# Eagle-V2-SunSensor.net
KiCad netlist of a schematic drawn in EAGLE
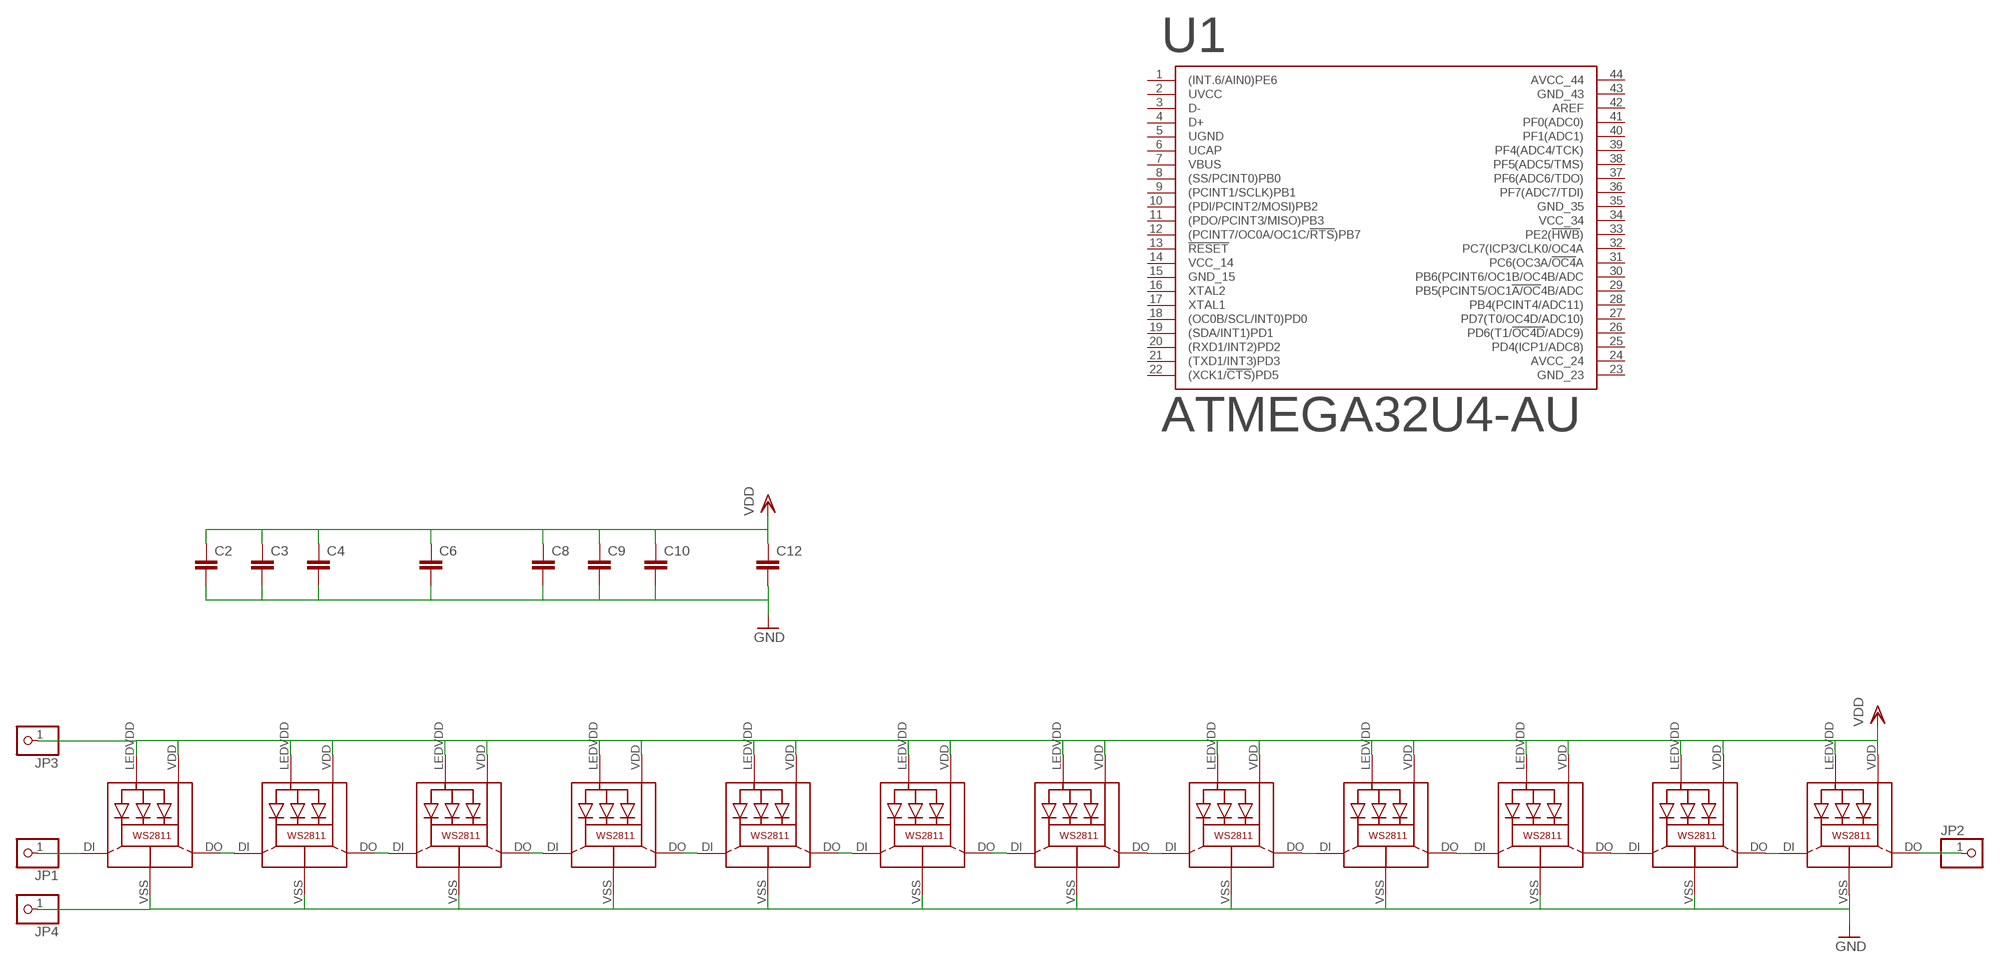
[diagram p0: schematic, sheet 1]

(export (version "E")
  (design (tool "Eeschema 10.0.6"))
  (components
    (comp (ref "C2")
      (value "C-EUC0603")
      (footprint "eagle-import:C0603")
      (libsource (lib "eagle-import") (part "C-EUC0603"))
    )
    (comp (ref "C3")
      (value "C-EUC0603")
      (footprint "eagle-import:C0603")
      (libsource (lib "eagle-import") (part "C-EUC0603"))
    )
    (comp (ref "C4")
      (value "C-EUC0603")
      (footprint "eagle-import:C0603")
      (libsource (lib "eagle-import") (part "C-EUC0603"))
    )
    (comp (ref "C6")
      (value "C-EUC0603")
      (footprint "eagle-import:C0603")
      (libsource (lib "eagle-import") (part "C-EUC0603"))
    )
    (comp (ref "C8")
      (value "C-EUC0603")
      (footprint "eagle-import:C0603")
      (libsource (lib "eagle-import") (part "C-EUC0603"))
    )
    (comp (ref "C9")
      (value "C-EUC0603")
      (footprint "eagle-import:C0603")
      (libsource (lib "eagle-import") (part "C-EUC0603"))
    )
    (comp (ref "C10")
      (value "C-EUC0603")
      (footprint "eagle-import:C0603")
      (libsource (lib "eagle-import") (part "C-EUC0603"))
    )
    (comp (ref "C12")
      (value "C-EUC0603")
      (footprint "eagle-import:C0603")
      (libsource (lib "eagle-import") (part "C-EUC0603"))
    )
    (comp (ref "JP1")
      (value "PINHD-1X1CB")
      (footprint "eagle-import:1X01-CLEANBIG")
      (libsource (lib "eagle-import") (part "PINHD-1X1CB"))
    )
    (comp (ref "JP2")
      (value "PINHD-1X1CB")
      (footprint "eagle-import:1X01-CLEANBIG")
      (libsource (lib "eagle-import") (part "PINHD-1X1CB"))
    )
    (comp (ref "JP3")
      (value "PINHD-1X1CB")
      (footprint "eagle-import:1X01-CLEANBIG")
      (libsource (lib "eagle-import") (part "PINHD-1X1CB"))
    )
    (comp (ref "JP4")
      (value "PINHD-1X1CB")
      (footprint "eagle-import:1X01-CLEANBIG")
      (libsource (lib "eagle-import") (part "PINHD-1X1CB"))
    )
    (comp (ref "LED1")
      (value "WS28115050")
      (footprint "eagle-import:WS28115050")
      (libsource (lib "eagle-import") (part "WS28115050"))
    )
    (comp (ref "LED2")
      (value "WS28115050")
      (footprint "eagle-import:WS28115050")
      (libsource (lib "eagle-import") (part "WS28115050"))
    )
    (comp (ref "LED3")
      (value "WS28115050")
      (footprint "eagle-import:WS28115050")
      (libsource (lib "eagle-import") (part "WS28115050"))
    )
    (comp (ref "LED4")
      (value "WS28115050")
      (footprint "eagle-import:WS28115050")
      (libsource (lib "eagle-import") (part "WS28115050"))
    )
    (comp (ref "LED5")
      (value "WS28115050")
      (footprint "eagle-import:WS28115050")
      (libsource (lib "eagle-import") (part "WS28115050"))
    )
    (comp (ref "LED6")
      (value "WS28115050")
      (footprint "eagle-import:WS28115050")
      (libsource (lib "eagle-import") (part "WS28115050"))
    )
    (comp (ref "LED7")
      (value "WS28115050")
      (footprint "eagle-import:WS28115050")
      (libsource (lib "eagle-import") (part "WS28115050"))
    )
    (comp (ref "LED8")
      (value "WS28115050")
      (footprint "eagle-import:WS28115050")
      (libsource (lib "eagle-import") (part "WS28115050"))
    )
    (comp (ref "LED9")
      (value "WS28115050")
      (footprint "eagle-import:WS28115050")
      (libsource (lib "eagle-import") (part "WS28115050"))
    )
    (comp (ref "LED10")
      (value "WS28115050")
      (footprint "eagle-import:WS28115050")
      (libsource (lib "eagle-import") (part "WS28115050"))
    )
    (comp (ref "LED11")
      (value "WS28115050")
      (footprint "eagle-import:WS28115050")
      (libsource (lib "eagle-import") (part "WS28115050"))
    )
    (comp (ref "LED12")
      (value "WS28115050")
      (footprint "eagle-import:WS28115050")
      (libsource (lib "eagle-import") (part "WS28115050"))
    )
    (comp (ref "U1")
      (value "ATMEGA32U4-AU")
      (footprint "eagle-import:44-TQFP")
      (fields
        (field (name "DIGIKEY_PART_NUMBER") "ATMEGA32U4-AU-ND")
        (field (name "MANUFACTURER") "Microchip Technology")
        (field (name "CREATED_BY") "PCBLayout.com")
      )
      (libsource (lib "eagle-import") (part "ATMEGA32U4-AU"))
    )
  )
  (nets
    (net (code "1") (name "/AVCC_24") (class "Default")
      (node (ref "U1") (pin "24") (pinfunction "AVCC_24_24") (pintype "power_in"))
    )
    (net (code "2") (name "/AVCC_44") (class "Default")
      (node (ref "U1") (pin "44") (pinfunction "AVCC_44_44") (pintype "power_in"))
    )
    (net (code "3") (name "/GND_15") (class "Default")
      (node (ref "U1") (pin "15") (pinfunction "GND_15_15") (pintype "power_in"))
    )
    (net (code "4") (name "/GND_23") (class "Default")
      (node (ref "U1") (pin "23") (pinfunction "GND_23_23") (pintype "power_in"))
    )
    (net (code "5") (name "/GND_35") (class "Default")
      (node (ref "U1") (pin "35") (pinfunction "GND_35_35") (pintype "power_in"))
    )
    (net (code "6") (name "/GND_43") (class "Default")
      (node (ref "U1") (pin "43") (pinfunction "GND_43_43") (pintype "power_in"))
    )
    (net (code "7") (name "/UCAP") (class "Default")
      (node (ref "U1") (pin "6") (pinfunction "UCAP_6") (pintype "power_in"))
    )
    (net (code "8") (name "/UGND") (class "Default")
      (node (ref "U1") (pin "5") (pinfunction "UGND_5") (pintype "power_in"))
    )
    (net (code "9") (name "/UVCC") (class "Default")
      (node (ref "U1") (pin "2") (pinfunction "UVCC_2") (pintype "power_in"))
    )
    (net (code "10") (name "/VCC_14") (class "Default")
      (node (ref "U1") (pin "14") (pinfunction "VCC_14_14") (pintype "power_in"))
    )
    (net (code "11") (name "/VCC_34") (class "Default")
      (node (ref "U1") (pin "34") (pinfunction "VCC_34_34") (pintype "power_in"))
    )
    (net (code "12") (name "GND") (class "Default")
      (node (ref "C10") (pin "2") (pinfunction "2_2") (pintype "passive"))
      (node (ref "C12") (pin "2") (pinfunction "2_2") (pintype "passive"))
      (node (ref "C2") (pin "2") (pinfunction "2_2") (pintype "passive"))
      (node (ref "C3") (pin "2") (pinfunction "2_2") (pintype "passive"))
      (node (ref "C4") (pin "2") (pinfunction "2_2") (pintype "passive"))
      (node (ref "C6") (pin "2") (pinfunction "2_2") (pintype "passive"))
      (node (ref "C8") (pin "2") (pinfunction "2_2") (pintype "passive"))
      (node (ref "C9") (pin "2") (pinfunction "2_2") (pintype "passive"))
      (node (ref "JP4") (pin "1") (pinfunction "1_1") (pintype "passive"))
      (node (ref "LED1") (pin "VSS") (pinfunction "GND_VSS") (pintype "power_in"))
      (node (ref "LED10") (pin "VSS") (pinfunction "GND_VSS") (pintype "power_in"))
      (node (ref "LED11") (pin "VSS") (pinfunction "GND_VSS") (pintype "power_in"))
      (node (ref "LED12") (pin "VSS") (pinfunction "GND_VSS") (pintype "power_in"))
      (node (ref "LED2") (pin "VSS") (pinfunction "GND_VSS") (pintype "power_in"))
      (node (ref "LED3") (pin "VSS") (pinfunction "GND_VSS") (pintype "power_in"))
      (node (ref "LED4") (pin "VSS") (pinfunction "GND_VSS") (pintype "power_in"))
      (node (ref "LED5") (pin "VSS") (pinfunction "GND_VSS") (pintype "power_in"))
      (node (ref "LED6") (pin "VSS") (pinfunction "GND_VSS") (pintype "power_in"))
      (node (ref "LED7") (pin "VSS") (pinfunction "GND_VSS") (pintype "power_in"))
      (node (ref "LED8") (pin "VSS") (pinfunction "GND_VSS") (pintype "power_in"))
      (node (ref "LED9") (pin "VSS") (pinfunction "GND_VSS") (pintype "power_in"))
    )
    (net (code "13") (name "Net-(JP1-Pad1)") (class "Default")
      (node (ref "JP1") (pin "1") (pinfunction "1_1") (pintype "passive"))
      (node (ref "LED1") (pin "DI") (pinfunction "DI_DI") (pintype "input"))
    )
    (net (code "14") (name "Net-(JP2-Pad1)") (class "Default")
      (node (ref "JP2") (pin "1") (pinfunction "1_1") (pintype "passive"))
      (node (ref "LED12") (pin "DO") (pinfunction "DO_DO") (pintype "output"))
    )
    (net (code "15") (name "Net-(LED1-PadDO)") (class "Default")
      (node (ref "LED1") (pin "DO") (pinfunction "DO_DO") (pintype "output"))
      (node (ref "LED2") (pin "DI") (pinfunction "DI_DI") (pintype "input"))
    )
    (net (code "16") (name "Net-(LED2-PadDO)") (class "Default")
      (node (ref "LED2") (pin "DO") (pinfunction "DO_DO") (pintype "output"))
      (node (ref "LED3") (pin "DI") (pinfunction "DI_DI") (pintype "input"))
    )
    (net (code "17") (name "Net-(LED3-PadDO)") (class "Default")
      (node (ref "LED3") (pin "DO") (pinfunction "DO_DO") (pintype "output"))
      (node (ref "LED4") (pin "DI") (pinfunction "DI_DI") (pintype "input"))
    )
    (net (code "18") (name "Net-(LED4-PadDO)") (class "Default")
      (node (ref "LED4") (pin "DO") (pinfunction "DO_DO") (pintype "output"))
      (node (ref "LED5") (pin "DI") (pinfunction "DI_DI") (pintype "input"))
    )
    (net (code "19") (name "Net-(LED5-PadDO)") (class "Default")
      (node (ref "LED5") (pin "DO") (pinfunction "DO_DO") (pintype "output"))
      (node (ref "LED6") (pin "DI") (pinfunction "DI_DI") (pintype "input"))
    )
    (net (code "20") (name "Net-(LED6-PadDO)") (class "Default")
      (node (ref "LED6") (pin "DO") (pinfunction "DO_DO") (pintype "output"))
      (node (ref "LED7") (pin "DI") (pinfunction "DI_DI") (pintype "input"))
    )
    (net (code "21") (name "Net-(LED7-PadDO)") (class "Default")
      (node (ref "LED7") (pin "DO") (pinfunction "DO_DO") (pintype "output"))
      (node (ref "LED8") (pin "DI") (pinfunction "DI_DI") (pintype "input"))
    )
    (net (code "22") (name "Net-(LED8-PadDO)") (class "Default")
      (node (ref "LED8") (pin "DO") (pinfunction "DO_DO") (pintype "output"))
      (node (ref "LED9") (pin "DI") (pinfunction "DI_DI") (pintype "input"))
    )
    (net (code "23") (name "Net-(LED10-PadDI)") (class "Default")
      (node (ref "LED10") (pin "DI") (pinfunction "DI_DI") (pintype "input"))
      (node (ref "LED9") (pin "DO") (pinfunction "DO_DO") (pintype "output"))
    )
    (net (code "24") (name "Net-(LED10-PadDO)") (class "Default")
      (node (ref "LED10") (pin "DO") (pinfunction "DO_DO") (pintype "output"))
      (node (ref "LED11") (pin "DI") (pinfunction "DI_DI") (pintype "input"))
    )
    (net (code "25") (name "Net-(LED11-PadDO)") (class "Default")
      (node (ref "LED11") (pin "DO") (pinfunction "DO_DO") (pintype "output"))
      (node (ref "LED12") (pin "DI") (pinfunction "DI_DI") (pintype "input"))
    )
    (net (code "26") (name "VDD") (class "Default")
      (node (ref "C10") (pin "1") (pinfunction "1_1") (pintype "passive"))
      (node (ref "C12") (pin "1") (pinfunction "1_1") (pintype "passive"))
      (node (ref "C2") (pin "1") (pinfunction "1_1") (pintype "passive"))
      (node (ref "C3") (pin "1") (pinfunction "1_1") (pintype "passive"))
      (node (ref "C4") (pin "1") (pinfunction "1_1") (pintype "passive"))
      (node (ref "C6") (pin "1") (pinfunction "1_1") (pintype "passive"))
      (node (ref "C8") (pin "1") (pinfunction "1_1") (pintype "passive"))
      (node (ref "C9") (pin "1") (pinfunction "1_1") (pintype "passive"))
      (node (ref "JP3") (pin "1") (pinfunction "1_1") (pintype "passive"))
      (node (ref "LED1") (pin "LEDVDD") (pinfunction "LEDVDD_LEDVDD") (pintype "power_in"))
      (node (ref "LED1") (pin "VDD") (pinfunction "VDD_VDD") (pintype "power_in"))
      (node (ref "LED10") (pin "LEDVDD") (pinfunction "LEDVDD_LEDVDD") (pintype "power_in"))
      (node (ref "LED10") (pin "VDD") (pinfunction "VDD_VDD") (pintype "power_in"))
      (node (ref "LED11") (pin "LEDVDD") (pinfunction "LEDVDD_LEDVDD") (pintype "power_in"))
      (node (ref "LED11") (pin "VDD") (pinfunction "VDD_VDD") (pintype "power_in"))
      (node (ref "LED12") (pin "LEDVDD") (pinfunction "LEDVDD_LEDVDD") (pintype "power_in"))
      (node (ref "LED12") (pin "VDD") (pinfunction "VDD_VDD") (pintype "power_in"))
      (node (ref "LED2") (pin "LEDVDD") (pinfunction "LEDVDD_LEDVDD") (pintype "power_in"))
      (node (ref "LED2") (pin "VDD") (pinfunction "VDD_VDD") (pintype "power_in"))
      (node (ref "LED3") (pin "LEDVDD") (pinfunction "LEDVDD_LEDVDD") (pintype "power_in"))
      (node (ref "LED3") (pin "VDD") (pinfunction "VDD_VDD") (pintype "power_in"))
      (node (ref "LED4") (pin "LEDVDD") (pinfunction "LEDVDD_LEDVDD") (pintype "power_in"))
      (node (ref "LED4") (pin "VDD") (pinfunction "VDD_VDD") (pintype "power_in"))
      (node (ref "LED5") (pin "LEDVDD") (pinfunction "LEDVDD_LEDVDD") (pintype "power_in"))
      (node (ref "LED5") (pin "VDD") (pinfunction "VDD_VDD") (pintype "power_in"))
      (node (ref "LED6") (pin "LEDVDD") (pinfunction "LEDVDD_LEDVDD") (pintype "power_in"))
      (node (ref "LED6") (pin "VDD") (pinfunction "VDD_VDD") (pintype "power_in"))
      (node (ref "LED7") (pin "LEDVDD") (pinfunction "LEDVDD_LEDVDD") (pintype "power_in"))
      (node (ref "LED7") (pin "VDD") (pinfunction "VDD_VDD") (pintype "power_in"))
      (node (ref "LED8") (pin "LEDVDD") (pinfunction "LEDVDD_LEDVDD") (pintype "power_in"))
      (node (ref "LED8") (pin "VDD") (pinfunction "VDD_VDD") (pintype "power_in"))
      (node (ref "LED9") (pin "LEDVDD") (pinfunction "LEDVDD_LEDVDD") (pintype "power_in"))
      (node (ref "LED9") (pin "VDD") (pinfunction "VDD_VDD") (pintype "power_in"))
    )
    (net (code "27") (name "unconnected-(U1-(INT.6{slash}AIN0)PE6-Pad1)") (class "Default")
      (node (ref "U1") (pin "1") (pinfunction "(INT.6/AIN0)PE6_1") (pintype "bidirectional"))
    )
    (net (code "28") (name "unconnected-(U1-(OC0B{slash}SCL{slash}INT0)PD0-Pad18)") (class "Default")
      (node (ref "U1") (pin "18") (pinfunction "(OC0B/SCL/INT0)PD0_18") (pintype "bidirectional"))
    )
    (net (code "29") (name "unconnected-(U1-(PCINT1{slash}SCLK)PB1-Pad9)") (class "Default")
      (node (ref "U1") (pin "9") (pinfunction "(PCINT1/SCLK)PB1_9") (pintype "bidirectional"))
    )
    (net (code "30") (name "unconnected-(U1-(PCINT7{slash}OC0A{slash}OC1C{slash}~{RTS})PB7-Pad12)") (class "Default")
      (node (ref "U1") (pin "12") (pinfunction "(PCINT7/OC0A/OC1C/~{RTS})PB7_12") (pintype "bidirectional"))
    )
    (net (code "31") (name "unconnected-(U1-(PDI{slash}PCINT2{slash}MOSI)PB2-Pad10)") (class "Default")
      (node (ref "U1") (pin "10") (pinfunction "(PDI/PCINT2/MOSI)PB2_10") (pintype "bidirectional"))
    )
    (net (code "32") (name "unconnected-(U1-(PDO{slash}PCINT3{slash}MISO)PB3-Pad11)") (class "Default")
      (node (ref "U1") (pin "11") (pinfunction "(PDO/PCINT3/MISO)PB3_11") (pintype "bidirectional"))
    )
    (net (code "33") (name "unconnected-(U1-(RXD1{slash}INT2)PD2-Pad20)") (class "Default")
      (node (ref "U1") (pin "20") (pinfunction "(RXD1/INT2)PD2_20") (pintype "bidirectional"))
    )
    (net (code "34") (name "unconnected-(U1-(SDA{slash}INT1)PD1-Pad19)") (class "Default")
      (node (ref "U1") (pin "19") (pinfunction "(SDA/INT1)PD1_19") (pintype "bidirectional"))
    )
    (net (code "35") (name "unconnected-(U1-(SS{slash}PCINT0)PB0-Pad8)") (class "Default")
      (node (ref "U1") (pin "8") (pinfunction "(SS/PCINT0)PB0_8") (pintype "bidirectional"))
    )
    (net (code "36") (name "unconnected-(U1-(TXD1{slash}INT3)PD3-Pad21)") (class "Default")
      (node (ref "U1") (pin "21") (pinfunction "(TXD1/INT3)PD3_21") (pintype "bidirectional"))
    )
    (net (code "37") (name "unconnected-(U1-(XCK1{slash}~{CTS})PD5-Pad22)") (class "Default")
      (node (ref "U1") (pin "22") (pinfunction "(XCK1/~{CTS})PD5_22") (pintype "bidirectional"))
    )
    (net (code "38") (name "unconnected-(U1-AREF-Pad42)") (class "Default")
      (node (ref "U1") (pin "42") (pinfunction "AREF_42") (pintype "input"))
    )
    (net (code "39") (name "unconnected-(U1-D+-Pad4)") (class "Default")
      (node (ref "U1") (pin "4") (pinfunction "D+_4") (pintype "input"))
    )
    (net (code "40") (name "unconnected-(U1-D--Pad3)") (class "Default")
      (node (ref "U1") (pin "3") (pinfunction "D-_3") (pintype "input"))
    )
    (net (code "41") (name "unconnected-(U1-PB4(PCINT4{slash}ADC11)-Pad28)") (class "Default")
      (node (ref "U1") (pin "28") (pinfunction "PB4(PCINT4/ADC11)_28") (pintype "bidirectional"))
    )
    (net (code "42") (name "unconnected-(U1-PB5(PCINT5{slash}OC1~{A{slash}OC}4B{slash}ADC-Pad29)") (class "Default")
      (node (ref "U1") (pin "29") (pinfunction "PB5(PCINT5/OC1~{A/OC}4B/ADC_29") (pintype "bidirectional"))
    )
    (net (code "43") (name "unconnected-(U1-PB6(PCINT6{slash}OC1B{slash}OC4B{slash}ADC-Pad30)") (class "Default")
      (node (ref "U1") (pin "30") (pinfunction "PB6(PCINT6/OC1B/OC4B/ADC_30") (pintype "bidirectional"))
    )
    (net (code "44") (name "unconnected-(U1-PC6(OC3A{slash}~{OC4}A-Pad31)") (class "Default")
      (node (ref "U1") (pin "31") (pinfunction "PC6(OC3A/~{OC4}A_31") (pintype "bidirectional"))
    )
    (net (code "45") (name "unconnected-(U1-PC7(ICP3{slash}CLK0{slash}OC4A-Pad32)") (class "Default")
      (node (ref "U1") (pin "32") (pinfunction "PC7(ICP3/CLK0/OC4A_32") (pintype "bidirectional"))
    )
    (net (code "46") (name "unconnected-(U1-PD4(ICP1{slash}ADC8)-Pad25)") (class "Default")
      (node (ref "U1") (pin "25") (pinfunction "PD4(ICP1/ADC8)_25") (pintype "bidirectional"))
    )
    (net (code "47") (name "unconnected-(U1-PD6(T1{slash}~{OC4D}{slash}ADC9)-Pad26)") (class "Default")
      (node (ref "U1") (pin "26") (pinfunction "PD6(T1/~{OC4D}/ADC9)_26") (pintype "bidirectional"))
    )
    (net (code "48") (name "unconnected-(U1-PD7(T0{slash}OC4D{slash}ADC10)-Pad27)") (class "Default")
      (node (ref "U1") (pin "27") (pinfunction "PD7(T0/OC4D/ADC10)_27") (pintype "bidirectional"))
    )
    (net (code "49") (name "unconnected-(U1-PE2(~{HWB})-Pad33)") (class "Default")
      (node (ref "U1") (pin "33") (pinfunction "PE2(~{HWB})_33") (pintype "bidirectional"))
    )
    (net (code "50") (name "unconnected-(U1-PF0(ADC0)-Pad41)") (class "Default")
      (node (ref "U1") (pin "41") (pinfunction "PF0(ADC0)_41") (pintype "bidirectional"))
    )
    (net (code "51") (name "unconnected-(U1-PF1(ADC1)-Pad40)") (class "Default")
      (node (ref "U1") (pin "40") (pinfunction "PF1(ADC1)_40") (pintype "bidirectional"))
    )
    (net (code "52") (name "unconnected-(U1-PF4(ADC4{slash}TCK)-Pad39)") (class "Default")
      (node (ref "U1") (pin "39") (pinfunction "PF4(ADC4/TCK)_39") (pintype "bidirectional"))
    )
    (net (code "53") (name "unconnected-(U1-PF5(ADC5{slash}TMS)-Pad38)") (class "Default")
      (node (ref "U1") (pin "38") (pinfunction "PF5(ADC5/TMS)_38") (pintype "bidirectional"))
    )
    (net (code "54") (name "unconnected-(U1-PF6(ADC6{slash}TDO)-Pad37)") (class "Default")
      (node (ref "U1") (pin "37") (pinfunction "PF6(ADC6/TDO)_37") (pintype "bidirectional"))
    )
    (net (code "55") (name "unconnected-(U1-PF7(ADC7{slash}TDI)-Pad36)") (class "Default")
      (node (ref "U1") (pin "36") (pinfunction "PF7(ADC7/TDI)_36") (pintype "bidirectional"))
    )
    (net (code "56") (name "unconnected-(U1-VBUS-Pad7)") (class "Default")
      (node (ref "U1") (pin "7") (pinfunction "VBUS_7") (pintype "input"))
    )
    (net (code "57") (name "unconnected-(U1-XTAL1-Pad17)") (class "Default")
      (node (ref "U1") (pin "17") (pinfunction "XTAL1_17") (pintype "input"))
    )
    (net (code "58") (name "unconnected-(U1-XTAL2-Pad16)") (class "Default")
      (node (ref "U1") (pin "16") (pinfunction "XTAL2_16") (pintype "output"))
    )
    (net (code "59") (name "unconnected-(U1-~{RESET}-Pad13)") (class "Default")
      (node (ref "U1") (pin "13") (pinfunction "~{RESET}_13") (pintype "input"))
    )
  )
)
